# DigitalSupplies.net
KiCad netlist of a schematic drawn in Altium Designer
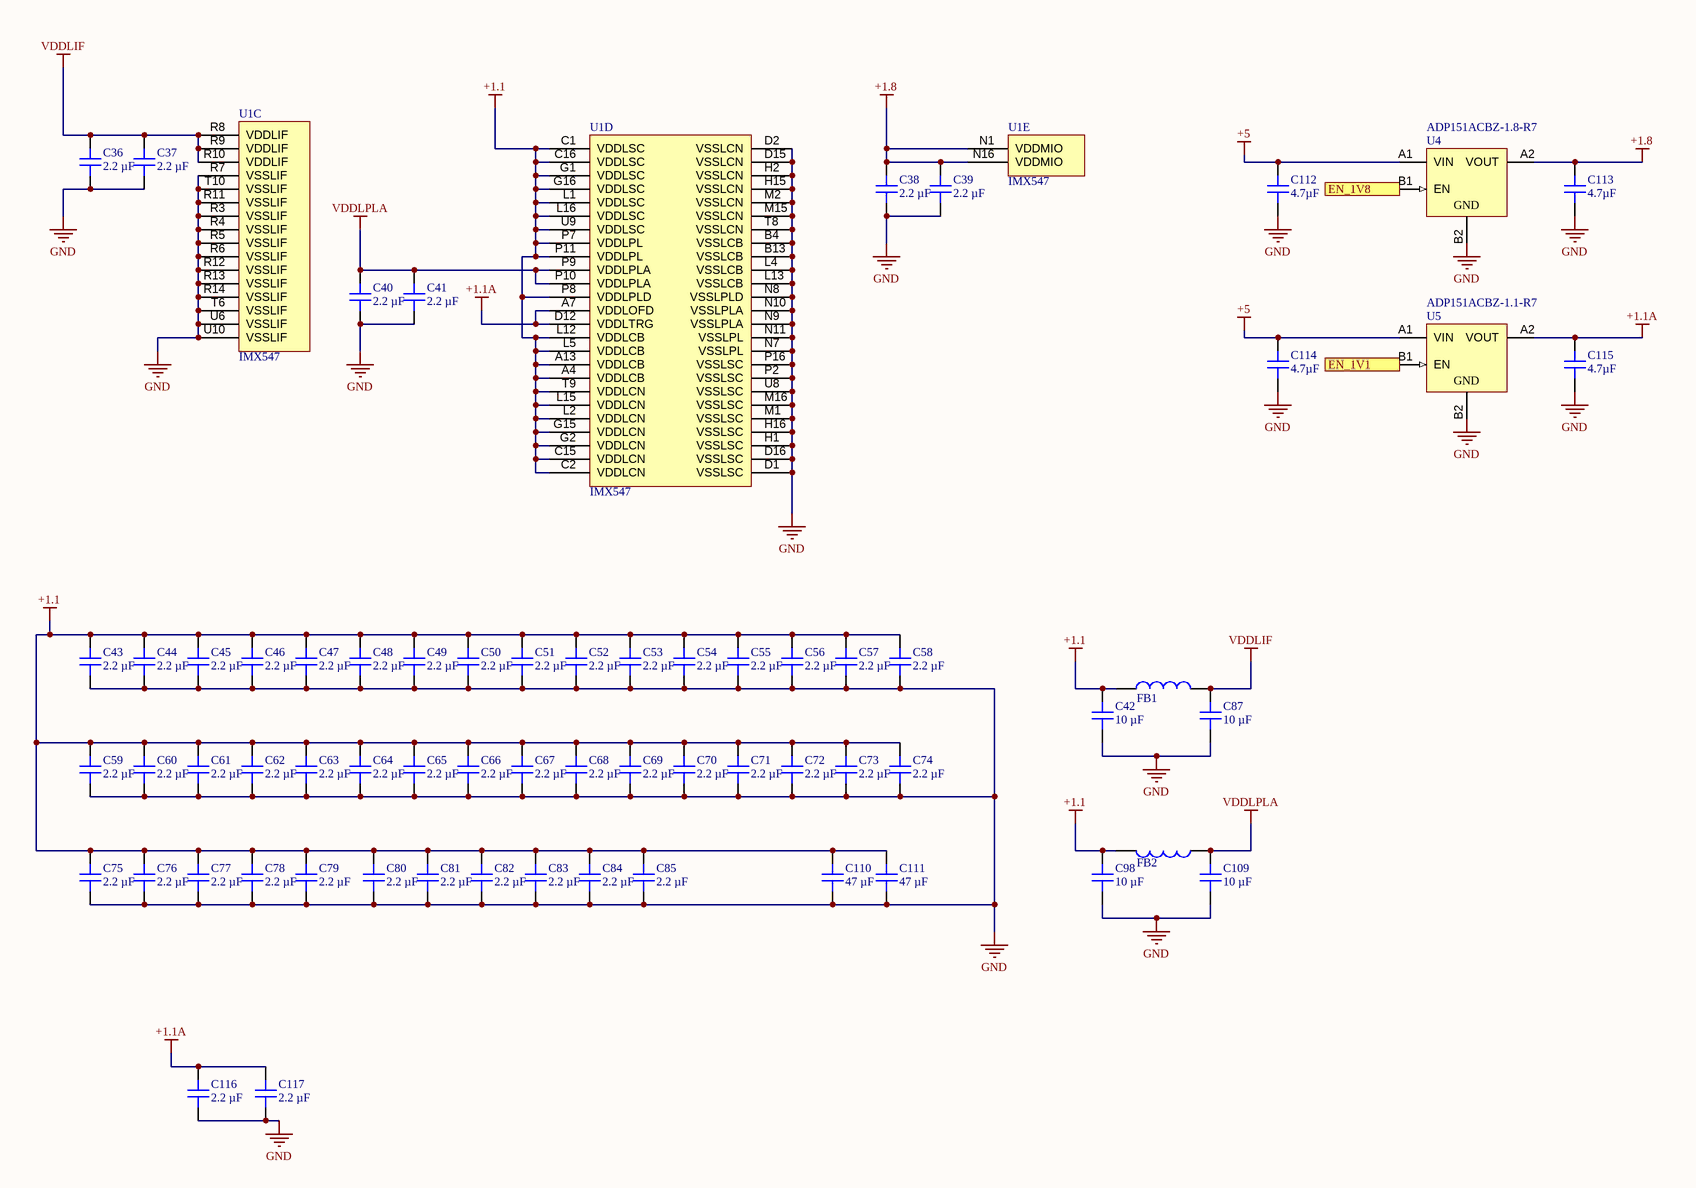
[diagram p0: DigitalSupplies.SchDoc]

(export (version "E")
  (design (tool "Eeschema 10.0.6"))
  (components
    (comp (ref "C36")
      (value "2.2 µF")
      (footprint "FP-GRM033-0_09-MFG")
      (description "CAP CER 2.2UF 6.3V X5R 0201")
      (fields
        (field (name "PART NUMBER") "GRM033R60J225ME01D")
        (field (name "MANUFACTURER") "Murata Electronics")
      )
      (libsource (lib "Celestial Altium Library - altium_library") (part "Capacitor"))
    )
    (comp (ref "C37")
      (value "2.2 µF")
      (footprint "FP-GRM033-0_09-MFG")
      (description "CAP CER 2.2UF 6.3V X5R 0201")
      (fields
        (field (name "PART NUMBER") "GRM033R60J225ME01D")
        (field (name "MANUFACTURER") "Murata Electronics")
      )
      (libsource (lib "Celestial Altium Library - altium_library") (part "Capacitor"))
    )
    (comp (ref "C38")
      (value "2.2 µF")
      (footprint "FP-GRM033-0_09-MFG")
      (description "CAP CER 2.2UF 6.3V X5R 0201")
      (fields
        (field (name "PART NUMBER") "GRM033R60J225ME01D")
        (field (name "MANUFACTURER") "Murata Electronics")
      )
      (libsource (lib "Celestial Altium Library - altium_library") (part "Capacitor"))
    )
    (comp (ref "C39")
      (value "2.2 µF")
      (footprint "FP-GRM033-0_09-MFG")
      (description "CAP CER 2.2UF 6.3V X5R 0201")
      (fields
        (field (name "PART NUMBER") "GRM033R60J225ME01D")
        (field (name "MANUFACTURER") "Murata Electronics")
      )
      (libsource (lib "Celestial Altium Library - altium_library") (part "Capacitor"))
    )
    (comp (ref "C40")
      (value "2.2 µF")
      (footprint "FP-GRM033-0_09-MFG")
      (description "CAP CER 2.2UF 6.3V X5R 0201")
      (fields
        (field (name "PART NUMBER") "GRM033R60J225ME01D")
        (field (name "MANUFACTURER") "Murata Electronics")
      )
      (libsource (lib "Celestial Altium Library - altium_library") (part "Capacitor"))
    )
    (comp (ref "C41")
      (value "2.2 µF")
      (footprint "FP-GRM033-0_09-MFG")
      (description "CAP CER 2.2UF 6.3V X5R 0201")
      (fields
        (field (name "PART NUMBER") "GRM033R60J225ME01D")
        (field (name "MANUFACTURER") "Murata Electronics")
      )
      (libsource (lib "Celestial Altium Library - altium_library") (part "Capacitor"))
    )
    (comp (ref "C42")
      (value "10 µF")
      (footprint "FP-GRM155-0_15-MFG")
      (description "CAP CER 10UF 6.3V X5R 0402")
      (fields
        (field (name "PART NUMBER") "GRM155R60J106ME15D")
        (field (name "MANUFACTURER") "Murata Electronics")
      )
      (libsource (lib "Celestial Altium Library - altium_library") (part "Capacitor"))
    )
    (comp (ref "C43")
      (value "2.2 µF")
      (footprint "FP-GRM033-0_09-MFG")
      (description "CAP CER 2.2UF 6.3V X5R 0201")
      (fields
        (field (name "PART NUMBER") "GRM033R60J225ME01D")
        (field (name "MANUFACTURER") "Murata Electronics")
      )
      (libsource (lib "Celestial Altium Library - altium_library") (part "Capacitor"))
    )
    (comp (ref "C44")
      (value "2.2 µF")
      (footprint "FP-GRM033-0_09-MFG")
      (description "CAP CER 2.2UF 6.3V X5R 0201")
      (fields
        (field (name "PART NUMBER") "GRM033R60J225ME01D")
        (field (name "MANUFACTURER") "Murata Electronics")
      )
      (libsource (lib "Celestial Altium Library - altium_library") (part "Capacitor"))
    )
    (comp (ref "C45")
      (value "2.2 µF")
      (footprint "FP-GRM033-0_09-MFG")
      (description "CAP CER 2.2UF 6.3V X5R 0201")
      (fields
        (field (name "PART NUMBER") "GRM033R60J225ME01D")
        (field (name "MANUFACTURER") "Murata Electronics")
      )
      (libsource (lib "Celestial Altium Library - altium_library") (part "Capacitor"))
    )
    (comp (ref "C46")
      (value "2.2 µF")
      (footprint "FP-GRM033-0_09-MFG")
      (description "CAP CER 2.2UF 6.3V X5R 0201")
      (fields
        (field (name "PART NUMBER") "GRM033R60J225ME01D")
        (field (name "MANUFACTURER") "Murata Electronics")
      )
      (libsource (lib "Celestial Altium Library - altium_library") (part "Capacitor"))
    )
    (comp (ref "C47")
      (value "2.2 µF")
      (footprint "FP-GRM033-0_09-MFG")
      (description "CAP CER 2.2UF 6.3V X5R 0201")
      (fields
        (field (name "PART NUMBER") "GRM033R60J225ME01D")
        (field (name "MANUFACTURER") "Murata Electronics")
      )
      (libsource (lib "Celestial Altium Library - altium_library") (part "Capacitor"))
    )
    (comp (ref "C48")
      (value "2.2 µF")
      (footprint "FP-GRM033-0_09-MFG")
      (description "CAP CER 2.2UF 6.3V X5R 0201")
      (fields
        (field (name "PART NUMBER") "GRM033R60J225ME01D")
        (field (name "MANUFACTURER") "Murata Electronics")
      )
      (libsource (lib "Celestial Altium Library - altium_library") (part "Capacitor"))
    )
    (comp (ref "C49")
      (value "2.2 µF")
      (footprint "FP-GRM033-0_09-MFG")
      (description "CAP CER 2.2UF 6.3V X5R 0201")
      (fields
        (field (name "PART NUMBER") "GRM033R60J225ME01D")
        (field (name "MANUFACTURER") "Murata Electronics")
      )
      (libsource (lib "Celestial Altium Library - altium_library") (part "Capacitor"))
    )
    (comp (ref "C50")
      (value "2.2 µF")
      (footprint "FP-GRM033-0_09-MFG")
      (description "CAP CER 2.2UF 6.3V X5R 0201")
      (fields
        (field (name "PART NUMBER") "GRM033R60J225ME01D")
        (field (name "MANUFACTURER") "Murata Electronics")
      )
      (libsource (lib "Celestial Altium Library - altium_library") (part "Capacitor"))
    )
    (comp (ref "C51")
      (value "2.2 µF")
      (footprint "FP-GRM033-0_09-MFG")
      (description "CAP CER 2.2UF 6.3V X5R 0201")
      (fields
        (field (name "PART NUMBER") "GRM033R60J225ME01D")
        (field (name "MANUFACTURER") "Murata Electronics")
      )
      (libsource (lib "Celestial Altium Library - altium_library") (part "Capacitor"))
    )
    (comp (ref "C52")
      (value "2.2 µF")
      (footprint "FP-GRM033-0_09-MFG")
      (description "CAP CER 2.2UF 6.3V X5R 0201")
      (fields
        (field (name "PART NUMBER") "GRM033R60J225ME01D")
        (field (name "MANUFACTURER") "Murata Electronics")
      )
      (libsource (lib "Celestial Altium Library - altium_library") (part "Capacitor"))
    )
    (comp (ref "C53")
      (value "2.2 µF")
      (footprint "FP-GRM033-0_09-MFG")
      (description "CAP CER 2.2UF 6.3V X5R 0201")
      (fields
        (field (name "PART NUMBER") "GRM033R60J225ME01D")
        (field (name "MANUFACTURER") "Murata Electronics")
      )
      (libsource (lib "Celestial Altium Library - altium_library") (part "Capacitor"))
    )
    (comp (ref "C54")
      (value "2.2 µF")
      (footprint "FP-GRM033-0_09-MFG")
      (description "CAP CER 2.2UF 6.3V X5R 0201")
      (fields
        (field (name "PART NUMBER") "GRM033R60J225ME01D")
        (field (name "MANUFACTURER") "Murata Electronics")
      )
      (libsource (lib "Celestial Altium Library - altium_library") (part "Capacitor"))
    )
    (comp (ref "C55")
      (value "2.2 µF")
      (footprint "FP-GRM033-0_09-MFG")
      (description "CAP CER 2.2UF 6.3V X5R 0201")
      (fields
        (field (name "PART NUMBER") "GRM033R60J225ME01D")
        (field (name "MANUFACTURER") "Murata Electronics")
      )
      (libsource (lib "Celestial Altium Library - altium_library") (part "Capacitor"))
    )
    (comp (ref "C56")
      (value "2.2 µF")
      (footprint "FP-GRM033-0_09-MFG")
      (description "CAP CER 2.2UF 6.3V X5R 0201")
      (fields
        (field (name "PART NUMBER") "GRM033R60J225ME01D")
        (field (name "MANUFACTURER") "Murata Electronics")
      )
      (libsource (lib "Celestial Altium Library - altium_library") (part "Capacitor"))
    )
    (comp (ref "C57")
      (value "2.2 µF")
      (footprint "FP-GRM033-0_09-MFG")
      (description "CAP CER 2.2UF 6.3V X5R 0201")
      (fields
        (field (name "PART NUMBER") "GRM033R60J225ME01D")
        (field (name "MANUFACTURER") "Murata Electronics")
      )
      (libsource (lib "Celestial Altium Library - altium_library") (part "Capacitor"))
    )
    (comp (ref "C58")
      (value "2.2 µF")
      (footprint "FP-GRM033-0_09-MFG")
      (description "CAP CER 2.2UF 6.3V X5R 0201")
      (fields
        (field (name "PART NUMBER") "GRM033R60J225ME01D")
        (field (name "MANUFACTURER") "Murata Electronics")
      )
      (libsource (lib "Celestial Altium Library - altium_library") (part "Capacitor"))
    )
    (comp (ref "C59")
      (value "2.2 µF")
      (footprint "FP-GRM033-0_09-MFG")
      (description "CAP CER 2.2UF 6.3V X5R 0201")
      (fields
        (field (name "PART NUMBER") "GRM033R60J225ME01D")
        (field (name "MANUFACTURER") "Murata Electronics")
      )
      (libsource (lib "Celestial Altium Library - altium_library") (part "Capacitor"))
    )
    (comp (ref "C60")
      (value "2.2 µF")
      (footprint "FP-GRM033-0_09-MFG")
      (description "CAP CER 2.2UF 6.3V X5R 0201")
      (fields
        (field (name "PART NUMBER") "GRM033R60J225ME01D")
        (field (name "MANUFACTURER") "Murata Electronics")
      )
      (libsource (lib "Celestial Altium Library - altium_library") (part "Capacitor"))
    )
    (comp (ref "C61")
      (value "2.2 µF")
      (footprint "FP-GRM033-0_09-MFG")
      (description "CAP CER 2.2UF 6.3V X5R 0201")
      (fields
        (field (name "PART NUMBER") "GRM033R60J225ME01D")
        (field (name "MANUFACTURER") "Murata Electronics")
      )
      (libsource (lib "Celestial Altium Library - altium_library") (part "Capacitor"))
    )
    (comp (ref "C62")
      (value "2.2 µF")
      (footprint "FP-GRM033-0_09-MFG")
      (description "CAP CER 2.2UF 6.3V X5R 0201")
      (fields
        (field (name "PART NUMBER") "GRM033R60J225ME01D")
        (field (name "MANUFACTURER") "Murata Electronics")
      )
      (libsource (lib "Celestial Altium Library - altium_library") (part "Capacitor"))
    )
    (comp (ref "C63")
      (value "2.2 µF")
      (footprint "FP-GRM033-0_09-MFG")
      (description "CAP CER 2.2UF 6.3V X5R 0201")
      (fields
        (field (name "PART NUMBER") "GRM033R60J225ME01D")
        (field (name "MANUFACTURER") "Murata Electronics")
      )
      (libsource (lib "Celestial Altium Library - altium_library") (part "Capacitor"))
    )
    (comp (ref "C64")
      (value "2.2 µF")
      (footprint "FP-GRM033-0_09-MFG")
      (description "CAP CER 2.2UF 6.3V X5R 0201")
      (fields
        (field (name "PART NUMBER") "GRM033R60J225ME01D")
        (field (name "MANUFACTURER") "Murata Electronics")
      )
      (libsource (lib "Celestial Altium Library - altium_library") (part "Capacitor"))
    )
    (comp (ref "C65")
      (value "2.2 µF")
      (footprint "FP-GRM033-0_09-MFG")
      (description "CAP CER 2.2UF 6.3V X5R 0201")
      (fields
        (field (name "PART NUMBER") "GRM033R60J225ME01D")
        (field (name "MANUFACTURER") "Murata Electronics")
      )
      (libsource (lib "Celestial Altium Library - altium_library") (part "Capacitor"))
    )
    (comp (ref "C66")
      (value "2.2 µF")
      (footprint "FP-GRM033-0_09-MFG")
      (description "CAP CER 2.2UF 6.3V X5R 0201")
      (fields
        (field (name "PART NUMBER") "GRM033R60J225ME01D")
        (field (name "MANUFACTURER") "Murata Electronics")
      )
      (libsource (lib "Celestial Altium Library - altium_library") (part "Capacitor"))
    )
    (comp (ref "C67")
      (value "2.2 µF")
      (footprint "FP-GRM033-0_09-MFG")
      (description "CAP CER 2.2UF 6.3V X5R 0201")
      (fields
        (field (name "PART NUMBER") "GRM033R60J225ME01D")
        (field (name "MANUFACTURER") "Murata Electronics")
      )
      (libsource (lib "Celestial Altium Library - altium_library") (part "Capacitor"))
    )
    (comp (ref "C68")
      (value "2.2 µF")
      (footprint "FP-GRM033-0_09-MFG")
      (description "CAP CER 2.2UF 6.3V X5R 0201")
      (fields
        (field (name "PART NUMBER") "GRM033R60J225ME01D")
        (field (name "MANUFACTURER") "Murata Electronics")
      )
      (libsource (lib "Celestial Altium Library - altium_library") (part "Capacitor"))
    )
    (comp (ref "C69")
      (value "2.2 µF")
      (footprint "FP-GRM033-0_09-MFG")
      (description "CAP CER 2.2UF 6.3V X5R 0201")
      (fields
        (field (name "PART NUMBER") "GRM033R60J225ME01D")
        (field (name "MANUFACTURER") "Murata Electronics")
      )
      (libsource (lib "Celestial Altium Library - altium_library") (part "Capacitor"))
    )
    (comp (ref "C70")
      (value "2.2 µF")
      (footprint "FP-GRM033-0_09-MFG")
      (description "CAP CER 2.2UF 6.3V X5R 0201")
      (fields
        (field (name "PART NUMBER") "GRM033R60J225ME01D")
        (field (name "MANUFACTURER") "Murata Electronics")
      )
      (libsource (lib "Celestial Altium Library - altium_library") (part "Capacitor"))
    )
    (comp (ref "C71")
      (value "2.2 µF")
      (footprint "FP-GRM033-0_09-MFG")
      (description "CAP CER 2.2UF 6.3V X5R 0201")
      (fields
        (field (name "PART NUMBER") "GRM033R60J225ME01D")
        (field (name "MANUFACTURER") "Murata Electronics")
      )
      (libsource (lib "Celestial Altium Library - altium_library") (part "Capacitor"))
    )
    (comp (ref "C72")
      (value "2.2 µF")
      (footprint "FP-GRM033-0_09-MFG")
      (description "CAP CER 2.2UF 6.3V X5R 0201")
      (fields
        (field (name "PART NUMBER") "GRM033R60J225ME01D")
        (field (name "MANUFACTURER") "Murata Electronics")
      )
      (libsource (lib "Celestial Altium Library - altium_library") (part "Capacitor"))
    )
    (comp (ref "C73")
      (value "2.2 µF")
      (footprint "FP-GRM033-0_09-MFG")
      (description "CAP CER 2.2UF 6.3V X5R 0201")
      (fields
        (field (name "PART NUMBER") "GRM033R60J225ME01D")
        (field (name "MANUFACTURER") "Murata Electronics")
      )
      (libsource (lib "Celestial Altium Library - altium_library") (part "Capacitor"))
    )
    (comp (ref "C74")
      (value "2.2 µF")
      (footprint "FP-GRM033-0_09-MFG")
      (description "CAP CER 2.2UF 6.3V X5R 0201")
      (fields
        (field (name "PART NUMBER") "GRM033R60J225ME01D")
        (field (name "MANUFACTURER") "Murata Electronics")
      )
      (libsource (lib "Celestial Altium Library - altium_library") (part "Capacitor"))
    )
    (comp (ref "C75")
      (value "2.2 µF")
      (footprint "FP-GRM033-0_09-MFG")
      (description "CAP CER 2.2UF 6.3V X5R 0201")
      (fields
        (field (name "PART NUMBER") "GRM033R60J225ME01D")
        (field (name "MANUFACTURER") "Murata Electronics")
      )
      (libsource (lib "Celestial Altium Library - altium_library") (part "Capacitor"))
    )
    (comp (ref "C76")
      (value "2.2 µF")
      (footprint "FP-GRM033-0_09-MFG")
      (description "CAP CER 2.2UF 6.3V X5R 0201")
      (fields
        (field (name "PART NUMBER") "GRM033R60J225ME01D")
        (field (name "MANUFACTURER") "Murata Electronics")
      )
      (libsource (lib "Celestial Altium Library - altium_library") (part "Capacitor"))
    )
    (comp (ref "C77")
      (value "2.2 µF")
      (footprint "FP-GRM033-0_09-MFG")
      (description "CAP CER 2.2UF 6.3V X5R 0201")
      (fields
        (field (name "PART NUMBER") "GRM033R60J225ME01D")
        (field (name "MANUFACTURER") "Murata Electronics")
      )
      (libsource (lib "Celestial Altium Library - altium_library") (part "Capacitor"))
    )
    (comp (ref "C78")
      (value "2.2 µF")
      (footprint "FP-GRM033-0_09-MFG")
      (description "CAP CER 2.2UF 6.3V X5R 0201")
      (fields
        (field (name "PART NUMBER") "GRM033R60J225ME01D")
        (field (name "MANUFACTURER") "Murata Electronics")
      )
      (libsource (lib "Celestial Altium Library - altium_library") (part "Capacitor"))
    )
    (comp (ref "C79")
      (value "2.2 µF")
      (footprint "FP-GRM033-0_09-MFG")
      (description "CAP CER 2.2UF 6.3V X5R 0201")
      (fields
        (field (name "PART NUMBER") "GRM033R60J225ME01D")
        (field (name "MANUFACTURER") "Murata Electronics")
      )
      (libsource (lib "Celestial Altium Library - altium_library") (part "Capacitor"))
    )
    (comp (ref "C80")
      (value "2.2 µF")
      (footprint "FP-GRM033-0_09-MFG")
      (description "CAP CER 2.2UF 6.3V X5R 0201")
      (fields
        (field (name "PART NUMBER") "GRM033R60J225ME01D")
        (field (name "MANUFACTURER") "Murata Electronics")
      )
      (libsource (lib "Celestial Altium Library - altium_library") (part "Capacitor"))
    )
    (comp (ref "C81")
      (value "2.2 µF")
      (footprint "FP-GRM033-0_09-MFG")
      (description "CAP CER 2.2UF 6.3V X5R 0201")
      (fields
        (field (name "PART NUMBER") "GRM033R60J225ME01D")
        (field (name "MANUFACTURER") "Murata Electronics")
      )
      (libsource (lib "Celestial Altium Library - altium_library") (part "Capacitor"))
    )
    (comp (ref "C82")
      (value "2.2 µF")
      (footprint "FP-GRM033-0_09-MFG")
      (description "CAP CER 2.2UF 6.3V X5R 0201")
      (fields
        (field (name "PART NUMBER") "GRM033R60J225ME01D")
        (field (name "MANUFACTURER") "Murata Electronics")
      )
      (libsource (lib "Celestial Altium Library - altium_library") (part "Capacitor"))
    )
    (comp (ref "C83")
      (value "2.2 µF")
      (footprint "FP-GRM033-0_09-MFG")
      (description "CAP CER 2.2UF 6.3V X5R 0201")
      (fields
        (field (name "PART NUMBER") "GRM033R60J225ME01D")
        (field (name "MANUFACTURER") "Murata Electronics")
      )
      (libsource (lib "Celestial Altium Library - altium_library") (part "Capacitor"))
    )
    (comp (ref "C84")
      (value "2.2 µF")
      (footprint "FP-GRM033-0_09-MFG")
      (description "CAP CER 2.2UF 6.3V X5R 0201")
      (fields
        (field (name "PART NUMBER") "GRM033R60J225ME01D")
        (field (name "MANUFACTURER") "Murata Electronics")
      )
      (libsource (lib "Celestial Altium Library - altium_library") (part "Capacitor"))
    )
    (comp (ref "C85")
      (value "2.2 µF")
      (footprint "FP-GRM033-0_09-MFG")
      (description "CAP CER 2.2UF 6.3V X5R 0201")
      (fields
        (field (name "PART NUMBER") "GRM033R60J225ME01D")
        (field (name "MANUFACTURER") "Murata Electronics")
      )
      (libsource (lib "Celestial Altium Library - altium_library") (part "Capacitor"))
    )
    (comp (ref "C87")
      (value "10 µF")
      (footprint "FP-GRM155-0_15-MFG")
      (description "CAP CER 10UF 6.3V X5R 0402")
      (fields
        (field (name "PART NUMBER") "GRM155R60J106ME15D")
        (field (name "MANUFACTURER") "Murata Electronics")
      )
      (libsource (lib "Celestial Altium Library - altium_library") (part "Capacitor"))
    )
    (comp (ref "C98")
      (value "10 µF")
      (footprint "FP-GRM155-0_15-MFG")
      (description "CAP CER 10UF 6.3V X5R 0402")
      (fields
        (field (name "PART NUMBER") "GRM155R60J106ME15D")
        (field (name "MANUFACTURER") "Murata Electronics")
      )
      (libsource (lib "Celestial Altium Library - altium_library") (part "Capacitor"))
    )
    (comp (ref "C109")
      (value "10 µF")
      (footprint "FP-GRM155-0_15-MFG")
      (description "CAP CER 10UF 6.3V X5R 0402")
      (fields
        (field (name "PART NUMBER") "GRM155R60J106ME15D")
        (field (name "MANUFACTURER") "Murata Electronics")
      )
      (libsource (lib "Celestial Altium Library - altium_library") (part "Capacitor"))
    )
    (comp (ref "C110")
      (value "47 µF")
      (footprint "FP-GRM188-0_15-MFG")
      (description "CAP CER 47UF 6.3V X5R 0603")
      (fields
        (field (name "PART NUMBER") "GRM188R60J476ME01D")
        (field (name "MANUFACTURER") "Murata Electronics")
      )
      (libsource (lib "Celestial Altium Library - altium_library") (part "Capacitor"))
    )
    (comp (ref "C111")
      (value "47 µF")
      (footprint "FP-GRM188-0_15-MFG")
      (description "CAP CER 47UF 6.3V X5R 0603")
      (fields
        (field (name "PART NUMBER") "GRM188R60J476ME01D")
        (field (name "MANUFACTURER") "Murata Electronics")
      )
      (libsource (lib "Celestial Altium Library - altium_library") (part "Capacitor"))
    )
    (comp (ref "C112")
      (value "4.7µF")
      (footprint "FP-GRM155-0_15-MFG")
      (description "CAP CER 4.7UF 10V X5R 0402")
      (fields
        (field (name "PART NUMBER") "GRM155R61A475MEAAD")
        (field (name "MANUFACTURER") "Murata Electronics")
      )
      (libsource (lib "Celestial Altium Library - altium_library") (part "Capacitor"))
    )
    (comp (ref "C113")
      (value "4.7µF")
      (footprint "FP-GRM155-0_15-MFG")
      (description "CAP CER 4.7UF 10V X5R 0402")
      (fields
        (field (name "PART NUMBER") "GRM155R61A475MEAAD")
        (field (name "MANUFACTURER") "Murata Electronics")
      )
      (libsource (lib "Celestial Altium Library - altium_library") (part "Capacitor"))
    )
    (comp (ref "C114")
      (value "4.7µF")
      (footprint "FP-GRM155-0_15-MFG")
      (description "CAP CER 4.7UF 10V X5R 0402")
      (fields
        (field (name "PART NUMBER") "GRM155R61A475MEAAD")
        (field (name "MANUFACTURER") "Murata Electronics")
      )
      (libsource (lib "Celestial Altium Library - altium_library") (part "Capacitor"))
    )
    (comp (ref "C115")
      (value "4.7µF")
      (footprint "FP-GRM155-0_15-MFG")
      (description "CAP CER 4.7UF 10V X5R 0402")
      (fields
        (field (name "PART NUMBER") "GRM155R61A475MEAAD")
        (field (name "MANUFACTURER") "Murata Electronics")
      )
      (libsource (lib "Celestial Altium Library - altium_library") (part "Capacitor"))
    )
    (comp (ref "C116")
      (value "2.2 µF")
      (footprint "FP-GRM033-0_09-MFG")
      (description "CAP CER 2.2UF 6.3V X5R 0201")
      (fields
        (field (name "PART NUMBER") "GRM033R60J225ME01D")
        (field (name "MANUFACTURER") "Murata Electronics")
      )
      (libsource (lib "Celestial Altium Library - altium_library") (part "Capacitor"))
    )
    (comp (ref "C117")
      (value "2.2 µF")
      (footprint "FP-GRM033-0_09-MFG")
      (description "CAP CER 2.2UF 6.3V X5R 0201")
      (fields
        (field (name "PART NUMBER") "GRM033R60J225ME01D")
        (field (name "MANUFACTURER") "Murata Electronics")
      )
      (libsource (lib "Celestial Altium Library - altium_library") (part "Capacitor"))
    )
    (comp (ref "FB1")
      (value "742843122")
      (footprint "WE-CBF HF_0402_High Current")
      (description "WE-CBF HF SMT High Frequency EMI Suppression Ferrite Bead, size 0402, 220O, 0.8A")
      (fields (field (name "MANUFACTURER") "Wurth Elektronik"))
      (libsource (lib "SimulaVR") (part "742863160"))
    )
    (comp (ref "FB2")
      (value "742843122")
      (footprint "WE-CBF HF_0402_High Current")
      (description "WE-CBF HF SMT High Frequency EMI Suppression Ferrite Bead, size 0402, 220O, 0.8A")
      (fields (field (name "MANUFACTURER") "Wurth Elektronik"))
      (libsource (lib "SimulaVR") (part "742863160"))
    )
    (comp (ref "U1")
      (value "IMX547")
      (footprint "LGA230C100P16X17_1680X2000X260")
      (description "Sony IMX547 sensor")
      (libsource (lib "David Kräutmann Beratung") (part "IMX547"))
    )
    (comp (ref "U4")
      (value "ADP151ACBZ-1.8-R7")
      (footprint "ADI-CB-4-3")
      (fields (field (name "MANUFACTURER") "Analog Devices"))
      (libsource (lib "Altium Content Vault") (part "ADI-ADP151-CB-4-3"))
    )
    (comp (ref "U5")
      (value "ADP151ACBZ-1.1-R7")
      (footprint "ADI-CB-4-3")
      (fields (field (name "MANUFACTURER") "Analog Devices"))
      (libsource (lib "Altium Content Vault") (part "ADI-ADP151-CB-4-3"))
    )
  )
  (nets
    (net (code "1") (name "+1.1") (class "Default")
      (node (ref "C110") (pin "2") (pinfunction "2_2") (pintype "passive"))
      (node (ref "C111") (pin "2") (pinfunction "2_2") (pintype "passive"))
      (node (ref "C42") (pin "2") (pinfunction "2_2") (pintype "passive"))
      (node (ref "C43") (pin "2") (pinfunction "2_2") (pintype "passive"))
      (node (ref "C44") (pin "2") (pinfunction "2_2") (pintype "passive"))
      (node (ref "C45") (pin "2") (pinfunction "2_2") (pintype "passive"))
      (node (ref "C46") (pin "2") (pinfunction "2_2") (pintype "passive"))
      (node (ref "C47") (pin "2") (pinfunction "2_2") (pintype "passive"))
      (node (ref "C48") (pin "2") (pinfunction "2_2") (pintype "passive"))
      (node (ref "C49") (pin "2") (pinfunction "2_2") (pintype "passive"))
      (node (ref "C50") (pin "2") (pinfunction "2_2") (pintype "passive"))
      (node (ref "C51") (pin "2") (pinfunction "2_2") (pintype "passive"))
      (node (ref "C52") (pin "2") (pinfunction "2_2") (pintype "passive"))
      (node (ref "C53") (pin "2") (pinfunction "2_2") (pintype "passive"))
      (node (ref "C54") (pin "2") (pinfunction "2_2") (pintype "passive"))
      (node (ref "C55") (pin "2") (pinfunction "2_2") (pintype "passive"))
      (node (ref "C56") (pin "2") (pinfunction "2_2") (pintype "passive"))
      (node (ref "C57") (pin "2") (pinfunction "2_2") (pintype "passive"))
      (node (ref "C58") (pin "2") (pinfunction "2_2") (pintype "passive"))
      (node (ref "C59") (pin "2") (pinfunction "2_2") (pintype "passive"))
      (node (ref "C60") (pin "2") (pinfunction "2_2") (pintype "passive"))
      (node (ref "C61") (pin "2") (pinfunction "2_2") (pintype "passive"))
      (node (ref "C62") (pin "2") (pinfunction "2_2") (pintype "passive"))
      (node (ref "C63") (pin "2") (pinfunction "2_2") (pintype "passive"))
      (node (ref "C64") (pin "2") (pinfunction "2_2") (pintype "passive"))
      (node (ref "C65") (pin "2") (pinfunction "2_2") (pintype "passive"))
      (node (ref "C66") (pin "2") (pinfunction "2_2") (pintype "passive"))
      (node (ref "C67") (pin "2") (pinfunction "2_2") (pintype "passive"))
      (node (ref "C68") (pin "2") (pinfunction "2_2") (pintype "passive"))
      (node (ref "C69") (pin "2") (pinfunction "2_2") (pintype "passive"))
      (node (ref "C70") (pin "2") (pinfunction "2_2") (pintype "passive"))
      (node (ref "C71") (pin "2") (pinfunction "2_2") (pintype "passive"))
      (node (ref "C72") (pin "2") (pinfunction "2_2") (pintype "passive"))
      (node (ref "C73") (pin "2") (pinfunction "2_2") (pintype "passive"))
      (node (ref "C74") (pin "2") (pinfunction "2_2") (pintype "passive"))
      (node (ref "C75") (pin "2") (pinfunction "2_2") (pintype "passive"))
      (node (ref "C76") (pin "2") (pinfunction "2_2") (pintype "passive"))
      (node (ref "C77") (pin "2") (pinfunction "2_2") (pintype "passive"))
      (node (ref "C78") (pin "2") (pinfunction "2_2") (pintype "passive"))
      (node (ref "C79") (pin "2") (pinfunction "2_2") (pintype "passive"))
      (node (ref "C80") (pin "2") (pinfunction "2_2") (pintype "passive"))
      (node (ref "C81") (pin "2") (pinfunction "2_2") (pintype "passive"))
      (node (ref "C82") (pin "2") (pinfunction "2_2") (pintype "passive"))
      (node (ref "C83") (pin "2") (pinfunction "2_2") (pintype "passive"))
      (node (ref "C84") (pin "2") (pinfunction "2_2") (pintype "passive"))
      (node (ref "C85") (pin "2") (pinfunction "2_2") (pintype "passive"))
      (node (ref "C98") (pin "2") (pinfunction "2_2") (pintype "passive"))
      (node (ref "FB1") (pin "1") (pinfunction "1_1") (pintype "passive"))
      (node (ref "FB2") (pin "2") (pinfunction "2_2") (pintype "passive"))
      (node (ref "U1") (pin "A13") (pinfunction "VDDLCB_A13") (pintype "power_in"))
      (node (ref "U1") (pin "A4") (pinfunction "VDDLCB_A4") (pintype "power_in"))
      (node (ref "U1") (pin "C1") (pinfunction "VDDLSC_C1") (pintype "power_in"))
      (node (ref "U1") (pin "C15") (pinfunction "VDDLCN_C15") (pintype "power_in"))
      (node (ref "U1") (pin "C16") (pinfunction "VDDLSC_C16") (pintype "power_in"))
      (node (ref "U1") (pin "C2") (pinfunction "VDDLCN_C2") (pintype "power_in"))
      (node (ref "U1") (pin "G1") (pinfunction "VDDLSC_G1") (pintype "power_in"))
      (node (ref "U1") (pin "G15") (pinfunction "VDDLCN_G15") (pintype "power_in"))
      (node (ref "U1") (pin "G16") (pinfunction "VDDLSC_G16") (pintype "power_in"))
      (node (ref "U1") (pin "G2") (pinfunction "VDDLCN_G2") (pintype "power_in"))
      (node (ref "U1") (pin "L1") (pinfunction "VDDLSC_L1") (pintype "power_in"))
      (node (ref "U1") (pin "L12") (pinfunction "VDDLCB_L12") (pintype "power_in"))
      (node (ref "U1") (pin "L15") (pinfunction "VDDLCN_L15") (pintype "power_in"))
      (node (ref "U1") (pin "L16") (pinfunction "VDDLSC_L16") (pintype "power_in"))
      (node (ref "U1") (pin "L2") (pinfunction "VDDLCN_L2") (pintype "power_in"))
      (node (ref "U1") (pin "L5") (pinfunction "VDDLCB_L5") (pintype "power_in"))
      (node (ref "U1") (pin "P11") (pinfunction "VDDLPL_P11") (pintype "power_in"))
      (node (ref "U1") (pin "P7") (pinfunction "VDDLPL_P7") (pintype "power_in"))
      (node (ref "U1") (pin "P8") (pinfunction "VDDLPLD_P8") (pintype "power_in"))
      (node (ref "U1") (pin "T9") (pinfunction "VDDLCN_T9") (pintype "power_in"))
      (node (ref "U1") (pin "U9") (pinfunction "VDDLSC_U9") (pintype "power_in"))
    )
    (net (code "2") (name "+1.1A") (class "Default")
      (node (ref "C115") (pin "2") (pinfunction "2_2") (pintype "passive"))
      (node (ref "C116") (pin "2") (pinfunction "2_2") (pintype "passive"))
      (node (ref "C117") (pin "2") (pinfunction "2_2") (pintype "passive"))
      (node (ref "U1") (pin "A7") (pinfunction "VDDLOFD_A7") (pintype "power_in"))
      (node (ref "U1") (pin "D12") (pinfunction "VDDLTRG_D12") (pintype "power_in"))
      (node (ref "U5") (pin "A2") (pinfunction "VOUT_A2") (pintype "power_in"))
    )
    (net (code "3") (name "+1.8") (class "Default")
      (node (ref "C113") (pin "2") (pinfunction "2_2") (pintype "passive"))
      (node (ref "C38") (pin "2") (pinfunction "2_2") (pintype "passive"))
      (node (ref "C39") (pin "2") (pinfunction "2_2") (pintype "passive"))
      (node (ref "U1") (pin "N1") (pinfunction "VDDMIO_N1") (pintype "power_in"))
      (node (ref "U1") (pin "N16") (pinfunction "VDDMIO_N16") (pintype "power_in"))
      (node (ref "U4") (pin "A2") (pinfunction "VOUT_A2") (pintype "power_in"))
    )
    (net (code "4") (name "+5") (class "Default")
      (node (ref "C112") (pin "2") (pinfunction "2_2") (pintype "passive"))
      (node (ref "C114") (pin "2") (pinfunction "2_2") (pintype "passive"))
      (node (ref "U4") (pin "A1") (pinfunction "VIN_A1") (pintype "power_in"))
      (node (ref "U5") (pin "A1") (pinfunction "VIN_A1") (pintype "power_in"))
    )
    (net (code "5") (name "/EN_1V1") (class "Default")
      (node (ref "U5") (pin "B1") (pinfunction "EN_B1") (pintype "input"))
    )
    (net (code "6") (name "/EN_1V8") (class "Default")
      (node (ref "U4") (pin "B1") (pinfunction "EN_B1") (pintype "input"))
    )
    (net (code "7") (name "GND") (class "Default")
      (node (ref "C109") (pin "1") (pinfunction "1_1") (pintype "passive"))
      (node (ref "C110") (pin "1") (pinfunction "1_1") (pintype "passive"))
      (node (ref "C111") (pin "1") (pinfunction "1_1") (pintype "passive"))
      (node (ref "C112") (pin "1") (pinfunction "1_1") (pintype "passive"))
      (node (ref "C113") (pin "1") (pinfunction "1_1") (pintype "passive"))
      (node (ref "C114") (pin "1") (pinfunction "1_1") (pintype "passive"))
      (node (ref "C115") (pin "1") (pinfunction "1_1") (pintype "passive"))
      (node (ref "C116") (pin "1") (pinfunction "1_1") (pintype "passive"))
      (node (ref "C117") (pin "1") (pinfunction "1_1") (pintype "passive"))
      (node (ref "C36") (pin "1") (pinfunction "1_1") (pintype "passive"))
      (node (ref "C37") (pin "1") (pinfunction "1_1") (pintype "passive"))
      (node (ref "C38") (pin "1") (pinfunction "1_1") (pintype "passive"))
      (node (ref "C39") (pin "1") (pinfunction "1_1") (pintype "passive"))
      (node (ref "C40") (pin "1") (pinfunction "1_1") (pintype "passive"))
      (node (ref "C41") (pin "1") (pinfunction "1_1") (pintype "passive"))
      (node (ref "C42") (pin "1") (pinfunction "1_1") (pintype "passive"))
      (node (ref "C43") (pin "1") (pinfunction "1_1") (pintype "passive"))
      (node (ref "C44") (pin "1") (pinfunction "1_1") (pintype "passive"))
      (node (ref "C45") (pin "1") (pinfunction "1_1") (pintype "passive"))
      (node (ref "C46") (pin "1") (pinfunction "1_1") (pintype "passive"))
      (node (ref "C47") (pin "1") (pinfunction "1_1") (pintype "passive"))
      (node (ref "C48") (pin "1") (pinfunction "1_1") (pintype "passive"))
      (node (ref "C49") (pin "1") (pinfunction "1_1") (pintype "passive"))
      (node (ref "C50") (pin "1") (pinfunction "1_1") (pintype "passive"))
      (node (ref "C51") (pin "1") (pinfunction "1_1") (pintype "passive"))
      (node (ref "C52") (pin "1") (pinfunction "1_1") (pintype "passive"))
      (node (ref "C53") (pin "1") (pinfunction "1_1") (pintype "passive"))
      (node (ref "C54") (pin "1") (pinfunction "1_1") (pintype "passive"))
      (node (ref "C55") (pin "1") (pinfunction "1_1") (pintype "passive"))
      (node (ref "C56") (pin "1") (pinfunction "1_1") (pintype "passive"))
      (node (ref "C57") (pin "1") (pinfunction "1_1") (pintype "passive"))
      (node (ref "C58") (pin "1") (pinfunction "1_1") (pintype "passive"))
      (node (ref "C59") (pin "1") (pinfunction "1_1") (pintype "passive"))
      (node (ref "C60") (pin "1") (pinfunction "1_1") (pintype "passive"))
      (node (ref "C61") (pin "1") (pinfunction "1_1") (pintype "passive"))
      (node (ref "C62") (pin "1") (pinfunction "1_1") (pintype "passive"))
      (node (ref "C63") (pin "1") (pinfunction "1_1") (pintype "passive"))
      (node (ref "C64") (pin "1") (pinfunction "1_1") (pintype "passive"))
      (node (ref "C65") (pin "1") (pinfunction "1_1") (pintype "passive"))
      (node (ref "C66") (pin "1") (pinfunction "1_1") (pintype "passive"))
      (node (ref "C67") (pin "1") (pinfunction "1_1") (pintype "passive"))
      (node (ref "C68") (pin "1") (pinfunction "1_1") (pintype "passive"))
      (node (ref "C69") (pin "1") (pinfunction "1_1") (pintype "passive"))
      (node (ref "C70") (pin "1") (pinfunction "1_1") (pintype "passive"))
      (node (ref "C71") (pin "1") (pinfunction "1_1") (pintype "passive"))
      (node (ref "C72") (pin "1") (pinfunction "1_1") (pintype "passive"))
      (node (ref "C73") (pin "1") (pinfunction "1_1") (pintype "passive"))
      (node (ref "C74") (pin "1") (pinfunction "1_1") (pintype "passive"))
      (node (ref "C75") (pin "1") (pinfunction "1_1") (pintype "passive"))
      (node (ref "C76") (pin "1") (pinfunction "1_1") (pintype "passive"))
      (node (ref "C77") (pin "1") (pinfunction "1_1") (pintype "passive"))
      (node (ref "C78") (pin "1") (pinfunction "1_1") (pintype "passive"))
      (node (ref "C79") (pin "1") (pinfunction "1_1") (pintype "passive"))
      (node (ref "C80") (pin "1") (pinfunction "1_1") (pintype "passive"))
      (node (ref "C81") (pin "1") (pinfunction "1_1") (pintype "passive"))
      (node (ref "C82") (pin "1") (pinfunction "1_1") (pintype "passive"))
      (node (ref "C83") (pin "1") (pinfunction "1_1") (pintype "passive"))
      (node (ref "C84") (pin "1") (pinfunction "1_1") (pintype "passive"))
      (node (ref "C85") (pin "1") (pinfunction "1_1") (pintype "passive"))
      (node (ref "C87") (pin "1") (pinfunction "1_1") (pintype "passive"))
      (node (ref "C98") (pin "1") (pinfunction "1_1") (pintype "passive"))
      (node (ref "U1") (pin "B13") (pinfunction "VSSLCB_B13") (pintype "power_in"))
      (node (ref "U1") (pin "B4") (pinfunction "VSSLCB_B4") (pintype "power_in"))
      (node (ref "U1") (pin "D1") (pinfunction "VSSLSC_D1") (pintype "power_in"))
      (node (ref "U1") (pin "D15") (pinfunction "VSSLCN_D15") (pintype "power_in"))
      (node (ref "U1") (pin "D16") (pinfunction "VSSLSC_D16") (pintype "power_in"))
      (node (ref "U1") (pin "D2") (pinfunction "VSSLCN_D2") (pintype "power_in"))
      (node (ref "U1") (pin "H1") (pinfunction "VSSLSC_H1") (pintype "power_in"))
      (node (ref "U1") (pin "H15") (pinfunction "VSSLCN_H15") (pintype "power_in"))
      (node (ref "U1") (pin "H16") (pinfunction "VSSLSC_H16") (pintype "power_in"))
      (node (ref "U1") (pin "H2") (pinfunction "VSSLCN_H2") (pintype "power_in"))
      (node (ref "U1") (pin "L13") (pinfunction "VSSLCB_L13") (pintype "power_in"))
      (node (ref "U1") (pin "L4") (pinfunction "VSSLCB_L4") (pintype "power_in"))
      (node (ref "U1") (pin "M1") (pinfunction "VSSLSC_M1") (pintype "power_in"))
      (node (ref "U1") (pin "M15") (pinfunction "VSSLCN_M15") (pintype "power_in"))
      (node (ref "U1") (pin "M16") (pinfunction "VSSLSC_M16") (pintype "power_in"))
      (node (ref "U1") (pin "M2") (pinfunction "VSSLCN_M2") (pintype "power_in"))
      (node (ref "U1") (pin "N10") (pinfunction "VSSLPLA_N10") (pintype "power_in"))
      (node (ref "U1") (pin "N11") (pinfunction "VSSLPL_N11") (pintype "power_in"))
      (node (ref "U1") (pin "N7") (pinfunction "VSSLPL_N7") (pintype "power_in"))
      (node (ref "U1") (pin "N8") (pinfunction "VSSLPLD_N8") (pintype "power_in"))
      (node (ref "U1") (pin "N9") (pinfunction "VSSLPLA_N9") (pintype "power_in"))
      (node (ref "U1") (pin "P16") (pinfunction "VSSLSC_P16") (pintype "power_in"))
      (node (ref "U1") (pin "P2") (pinfunction "VSSLSC_P2") (pintype "power_in"))
      (node (ref "U1") (pin "R11") (pinfunction "VSSLIF_R11") (pintype "power_in"))
      (node (ref "U1") (pin "R12") (pinfunction "VSSLIF_R12") (pintype "power_in"))
      (node (ref "U1") (pin "R13") (pinfunction "VSSLIF_R13") (pintype "power_in"))
      (node (ref "U1") (pin "R14") (pinfunction "VSSLIF_R14") (pintype "power_in"))
      (node (ref "U1") (pin "R3") (pinfunction "VSSLIF_R3") (pintype "power_in"))
      (node (ref "U1") (pin "R4") (pinfunction "VSSLIF_R4") (pintype "power_in"))
      (node (ref "U1") (pin "R5") (pinfunction "VSSLIF_R5") (pintype "power_in"))
      (node (ref "U1") (pin "R6") (pinfunction "VSSLIF_R6") (pintype "power_in"))
      (node (ref "U1") (pin "R7") (pinfunction "VSSLIF_R7") (pintype "power_in"))
      (node (ref "U1") (pin "T10") (pinfunction "VSSLIF_T10") (pintype "power_in"))
      (node (ref "U1") (pin "T6") (pinfunction "VSSLIF_T6") (pintype "power_in"))
      (node (ref "U1") (pin "T8") (pinfunction "VSSLCN_T8") (pintype "power_in"))
      (node (ref "U1") (pin "U10") (pinfunction "VSSLIF_U10") (pintype "power_in"))
      (node (ref "U1") (pin "U6") (pinfunction "VSSLIF_U6") (pintype "power_in"))
      (node (ref "U1") (pin "U8") (pinfunction "VSSLSC_U8") (pintype "power_in"))
      (node (ref "U4") (pin "B2") (pinfunction "GND_B2") (pintype "power_in"))
      (node (ref "U5") (pin "B2") (pinfunction "GND_B2") (pintype "power_in"))
    )
    (net (code "8") (name "VDDLIF") (class "Default")
      (node (ref "C36") (pin "2") (pinfunction "2_2") (pintype "passive"))
      (node (ref "C37") (pin "2") (pinfunction "2_2") (pintype "passive"))
      (node (ref "C87") (pin "2") (pinfunction "2_2") (pintype "passive"))
      (node (ref "FB1") (pin "2") (pinfunction "2_2") (pintype "passive"))
      (node (ref "U1") (pin "R10") (pinfunction "VDDLIF_R10") (pintype "power_in"))
      (node (ref "U1") (pin "R8") (pinfunction "VDDLIF_R8") (pintype "power_in"))
      (node (ref "U1") (pin "R9") (pinfunction "VDDLIF_R9") (pintype "power_in"))
    )
    (net (code "9") (name "VDDLPLA") (class "Default")
      (node (ref "C109") (pin "2") (pinfunction "2_2") (pintype "passive"))
      (node (ref "C40") (pin "2") (pinfunction "2_2") (pintype "passive"))
      (node (ref "C41") (pin "2") (pinfunction "2_2") (pintype "passive"))
      (node (ref "FB2") (pin "1") (pinfunction "1_1") (pintype "passive"))
      (node (ref "U1") (pin "P10") (pinfunction "VDDLPLA_P10") (pintype "power_in"))
      (node (ref "U1") (pin "P9") (pinfunction "VDDLPLA_P9") (pintype "power_in"))
    )
  )
)
